# IsoDcDc-BSR033A.net
KiCad netlist of a schematic drawn in Altium Designer
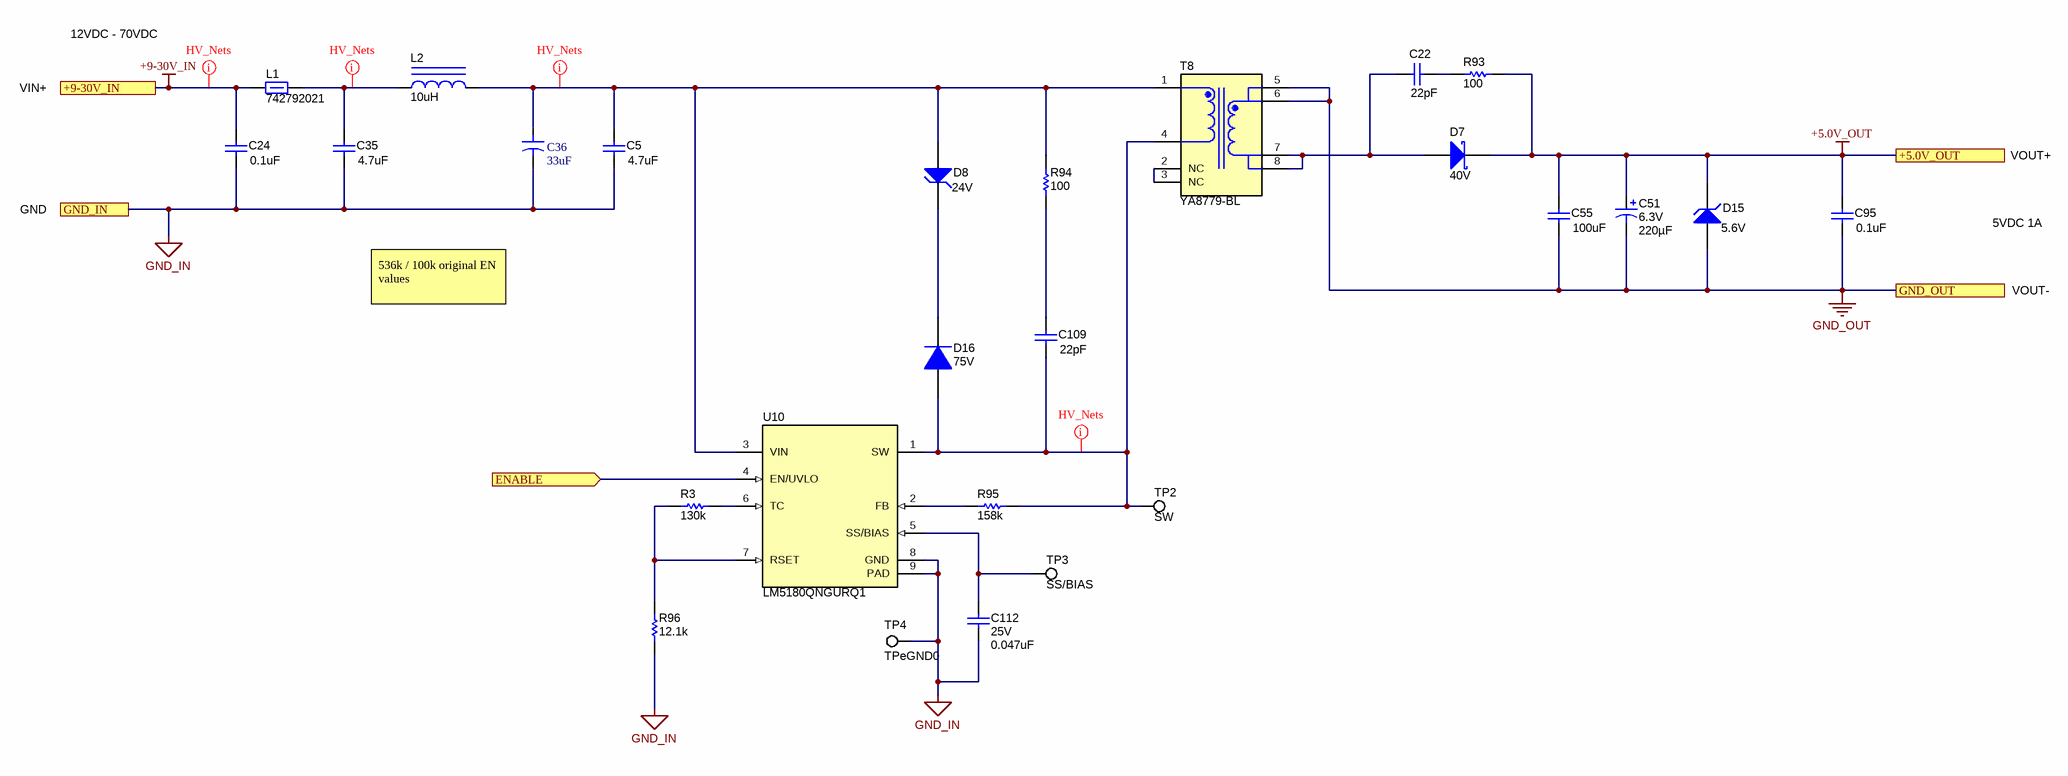
[diagram p0: IsoDcDc-BSR033A.SchDoc]

(export (version "E")
  (design (tool "Eeschema 10.0.6"))
  (components
    (comp (ref "C5")
      (value "GRM32DC72A475KE01L")
      (footprint "1210C")
      (description "CAP, CERM, 4.7 uF, 100 V, +/- 10%, X7S, 1210")
      (fields
        (field (name "MANUFACTURER") "MuRata")
        (field (name "VALUEDISPLAYED") "4.7uF")
        (field (name "PUBLISHER") "Texas Instruments")
      )
      (libsource (lib "BSR033A") (part "CMP-0009182-2"))
    )
    (comp (ref "C22")
      (value "GRM1885C2A220JA01D")
      (footprint "0603C")
      (description "CAP, CERM, 22 pF, 100 V, +/- 5%, C0G/NP0, 0603")
      (fields
        (field (name "MANUFACTURER") "MuRata")
        (field (name "VALUEDISPLAYED") "22pF")
        (field (name "PUBLISHER") "Texas Instruments")
      )
      (libsource (lib "BSR033A") (part "CMP-0007255-4"))
    )
    (comp (ref "C24")
      (value "GRM188R72A104KA35J")
      (footprint "0603C")
      (description "CAP, CERM, 0.1 uF, 100 V, +/- 10%, X7R, 0603")
      (fields
        (field (name "MANUFACTURER") "MuRata")
        (field (name "VALUEDISPLAYED") "0.1uF")
        (field (name "PUBLISHER") "Texas Instruments")
      )
      (libsource (lib "BSR033A") (part "CMP-0007470-5"))
    )
    (comp (ref "C35")
      (value "GRM32DC72A475KE01L")
      (footprint "1210C")
      (description "CAP, CERM, 4.7 uF, 100 V, +/- 10%, X7S, 1210")
      (fields
        (field (name "MANUFACTURER") "MuRata")
        (field (name "VALUEDISPLAYED") "4.7uF")
        (field (name "PUBLISHER") "Texas Instruments")
      )
      (libsource (lib "BSR033A") (part "CMP-0009182-2"))
    )
    (comp (ref "C36")
      (value "33uF")
      (footprint "CAPC7343X430M")
      (description "33µF Molded Tantalum Polymer Capacitor 50V 2917 (7343 Metric) 75mOhm @ 100kHz")
      (fields (field (name "Comment") "CAP TANTALUM 33UF 50V 2917"))
      (libsource (lib "master-010106") (part "T521X336M050ATE075"))
    )
    (comp (ref "C51")
      (value "T598D107M010ATE025")
      (footprint "7343-31")
      (description "CAP, Aluminum Polymer, 220 µF, 6.3 V,+/- 20%, 0.01 ohm, 7343-31 SMD")
      (fields
        (field (name "MANUFACTURER") "MuRata")
        (field (name "PARTNUMBER") "ECASD60J227M010K00")
        (field (name "VDC_V") "6.3V")
        (field (name "VALUEDISPLAYED") "220µF")
      )
      (libsource (lib "BSR033A") (part "Cap_Polarized"))
    )
    (comp (ref "C55")
      (value "GRM32EC80J107ME20L")
      (footprint "1210C")
      (description "CAP, CERM, 100 uF, 6.3 V, +/- 20%, X6S, 1210")
      (fields
        (field (name "MANUFACTURER") "MuRata")
        (field (name "VALUEDISPLAYED") "100uF")
        (field (name "PUBLISHER") "Texas Instruments")
      )
      (libsource (lib "BSR033A") (part "Capacitor"))
    )
    (comp (ref "C95")
      (value "GRM188R72A104KA35J")
      (footprint "0603C")
      (description "CAP, CERM, 0.1 uF, 100 V, +/- 10%, X7R, 0603")
      (fields
        (field (name "MANUFACTURER") "MuRata")
        (field (name "VALUEDISPLAYED") "0.1uF")
        (field (name "PUBLISHER") "Texas Instruments")
      )
      (libsource (lib "BSR033A") (part "CMP-0007470-5"))
    )
    (comp (ref "C109")
      (value "GRM1885C2A220JA01D")
      (footprint "0603C")
      (description "CAP, CERM, 22 pF, 100 V, +/- 5%, C0G/NP0, 0603")
      (fields
        (field (name "MANUFACTURER") "MuRata")
        (field (name "VALUEDISPLAYED") "22pF")
        (field (name "PUBLISHER") "Texas Instruments")
      )
      (libsource (lib "BSR033A") (part "CMP-0007255-4"))
    )
    (comp (ref "C112")
      (value "GCM188R71E473KA37D")
      (footprint "0603C")
      (description "CAP, CERM, 0.047 uF, 25 V, +/- 10%, X7R, AEC-Q200 Grade 1, 0603")
      (fields
        (field (name "MANUFACTURER") "MuRata")
        (field (name "VDC_V") "25V")
        (field (name "VALUEDISPLAYED") "0.047uF")
        (field (name "PUBLISHER") "Texas Instruments")
      )
      (libsource (lib "BSR033A") (part "CMP-0007141-5"))
    )
    (comp (ref "D7")
      (value "40V")
      (footprint "SMAF")
      (description "Diode, Schottky, 40 V, 3 A, AEC-Q101, SMAF")
      (fields
        (field (name "PARTNUMBER") "FSV340AF")
        (field (name "MANUFACTURER") "Fairchild Semiconductor")
        (field (name "PUBLISHER") "Texas Instruments")
      )
      (libsource (lib "BSR033A") (part "CMP-0028855-1"))
    )
    (comp (ref "D8")
      (value "DFLZ24-7")
      (footprint "PowerDI123")
      (description "Diode, Zener, 24 V, 1 W, PowerDI123")
      (fields
        (field (name "VZ_V") "24V")
        (field (name "MANUFACTURER") "Diodes Inc.")
        (field (name "PUBLISHER") "Texas Instruments")
      )
      (libsource (lib "BSR033A") (part "CMP-0005415-2"))
    )
    (comp (ref "D15")
      (value "MMSZ5232BS-7-F")
      (footprint "SOD-323")
      (description "Diode, Zener, 5.6 V, 200 mW, SOD-323")
      (fields
        (field (name "VZ_V") "5.6V")
        (field (name "MANUFACTURER") "Diodes Inc.")
        (field (name "PUBLISHER") "Texas Instruments")
      )
      (libsource (lib "BSR033A") (part "CMP-0005855-1"))
    )
    (comp (ref "D16")
      (value "75V")
      (footprint "SOD-323")
      (description "Diode, Ultrafast, 75 V, 0.25 A, SOD-323")
      (fields
        (field (name "MANUFACTURER") "Central Semiconductor")
        (field (name "PARTNUMBER") "CMDD4448")
        (field (name "PUBLISHER") "Texas Instruments")
      )
      (libsource (lib "BSR033A") (part "CMP-0029019-1"))
    )
    (comp (ref "L1")
      (value "742792021")
      (footprint "0805_HV")
      (description "Ferrite Bead, 22 ohm @ 100 MHz, 6 A, 0805")
      (fields (field (name "MANUFACTURER") "Wurth Elektronik") (field (name "PUBLISHER") "Texas Instruments"))
      (libsource (lib "BSR033A") (part "Ferrite_Bead"))
    )
    (comp (ref "L2")
      (value "744042100")
      (footprint "WE-TPC-M1")
      (description "Inductor, Shielded Drum Core, Ferrite, 10 uH, 1 A, 0.12 ohm, SMD")
      (fields
        (field (name "MANUFACTURER") "Wurth Elektronik")
        (field (name "VALUEDISPLAYED") "10uH")
        (field (name "PUBLISHER") "Texas Instruments")
      )
      (libsource (lib "BSR033A") (part "CMP-0063804-1"))
    )
    (comp (ref "R3")
      (value "CRCW0603130KFKEA")
      (footprint "0603R")
      (description "RES, 130 k, 1%, 0.1 W, AEC-Q200 Grade 0, 0603")
      (fields (field (name "MANUFACTURER") "Vishay-Dale") (field (name "VALUEDISPLAYED") "130k"))
      (libsource (lib "BSR033A") (part "CMP-0022036-4"))
    )
    (comp (ref "R93")
      (value "CRCW0603100RFKEA")
      (footprint "0603R")
      (description "RES, 100, 1%, 0.1 W, 0603")
      (fields
        (field (name "MANUFACTURER") "Vishay-Dale")
        (field (name "VALUEDISPLAYED") "100")
        (field (name "PUBLISHER") "Texas Instruments")
      )
      (libsource (lib "BSR033A") (part "CMP-0021991-3"))
    )
    (comp (ref "R94")
      (value "CRCW0603100RFKEA")
      (footprint "0603R")
      (description "RES, 100, 1%, 0.1 W, 0603")
      (fields
        (field (name "MANUFACTURER") "Vishay-Dale")
        (field (name "VALUEDISPLAYED") "100")
        (field (name "PUBLISHER") "Texas Instruments")
      )
      (libsource (lib "BSR033A") (part "CMP-0021991-3"))
    )
    (comp (ref "R95")
      (value "CRCW0603158KFKEA")
      (footprint "0603R")
      (description "RES, 158 k, 1%, 0.1 W, AEC-Q200 Grade 0, 0603")
      (fields (field (name "MANUFACTURER") "Vishay-Dale") (field (name "VALUEDISPLAYED") "158k"))
      (libsource (lib "BSR033A") (part "CMP-0022064-4"))
    )
    (comp (ref "R96")
      (value "CRCW060312K1FKEA")
      (footprint "0603R")
      (description "RES, 12.1 k, 1%, 0.1 W, 0603")
      (fields
        (field (name "MANUFACTURER") "Vishay-Dale")
        (field (name "VALUEDISPLAYED") "12.1k")
        (field (name "PUBLISHER") "Texas Instruments")
      )
      (libsource (lib "BSR033A") (part "CMP-0022030-3"))
    )
    (comp (ref "T8")
      (value "YA8779-BL")
      (footprint "Coilcraft_YA8779-CL")
      (description "Transformer, 30 uH, SMD")
      (fields (field (name "MANUFACTURER") "Coilcraft"))
      (libsource (lib "BSR033A") (part "Coilcraft_YA8779-CL"))
    )
    (comp (ref "TP2")
      (value "SW")
      (footprint "Testpoint_Keystone_Miniature")
      (description "Test Point, Miniature, SMT")
      (fields
        (field (name "MANUFACTURER") "Keystone")
        (field (name "PARTNUMBER") "5015")
        (field (name "PUBLISHER") "Texas Instruments")
      )
      (libsource (lib "Altium Vault - TI") (part "CMP-0055152-1"))
    )
    (comp (ref "TP3")
      (value "SS/BIAS")
      (footprint "Testpoint_Keystone_Miniature")
      (description "Test Point, Miniature, SMT")
      (fields
        (field (name "MANUFACTURER") "Keystone")
        (field (name "PARTNUMBER") "5015")
        (field (name "PUBLISHER") "Texas Instruments")
      )
      (libsource (lib "Altium Vault - TI") (part "CMP-0055152-1"))
    )
    (comp (ref "TP4")
      (value "TPeGND0")
      (footprint "Testpoint_Keystone_Miniature")
      (description "Test Point, Miniature, SMT")
      (fields
        (field (name "MANUFACTURER") "Keystone")
        (field (name "PARTNUMBER") "5015")
        (field (name "PUBLISHER") "Texas Instruments")
      )
      (libsource (lib "Altium Vault - TI") (part "CMP-0055152-1"))
    )
    (comp (ref "U10")
      (value "LM5180QNGURQ1")
      (footprint "NGU0008C")
      (description "70-V PSR Flyback Converter With 100-V, 1.2-A Power Switch and Ultra-Low IQ, NGU0008C (WSON-8)")
      (fields
        (field (name "ALTERNATE PARTNUMBER") "LM5180QNGUTQ1")
        (field (name "MANUFACTURER") "Texas Instruments")
        (field (name "PARTNUMBER") "LM5180QNGURQ1")
      )
      (libsource (lib "BSR033A") (part "LM5180-Q1"))
    )
  )
  (nets
    (net (code "1") (name "+5.0V_OUT") (class "Default")
      (node (ref "C51") (pin "1") (pinfunction "+_1") (pintype "passive"))
      (node (ref "C55") (pin "1") (pinfunction "1_1") (pintype "passive"))
      (node (ref "C95") (pin "1") (pinfunction "1_1") (pintype "passive"))
      (node (ref "D15") (pin "1") (pinfunction "K_1") (pintype "passive"))
      (node (ref "D7") (pin "1") (pinfunction "K_1") (pintype "passive"))
      (node (ref "R93") (pin "1") (pinfunction "1_1") (pintype "passive"))
    )
    (net (code "2") (name "+9-30V_IN") (class "Default")
      (node (ref "C24") (pin "1") (pinfunction "1_1") (pintype "passive"))
      (node (ref "L1") (pin "1") (pinfunction "1_1") (pintype "passive"))
    )
    (net (code "3") (name "/ENABLE") (class "Default")
      (node (ref "U10") (pin "4") (pinfunction "EN/UVLO_4") (pintype "input"))
    )
    (net (code "4") (name "GND_IN") (class "Default")
      (node (ref "C112") (pin "2") (pinfunction "2_2") (pintype "passive"))
      (node (ref "C24") (pin "2") (pinfunction "2_2") (pintype "passive"))
      (node (ref "C35") (pin "1") (pinfunction "1_1") (pintype "passive"))
      (node (ref "C36") (pin "2") (pinfunction "2_2") (pintype "passive"))
      (node (ref "C5") (pin "1") (pinfunction "1_1") (pintype "passive"))
      (node (ref "R96") (pin "1") (pinfunction "1_1") (pintype "passive"))
      (node (ref "TP4") (pin "1") (pintype "passive"))
      (node (ref "U10") (pin "8") (pinfunction "GND_8") (pintype "power_in"))
      (node (ref "U10") (pin "9") (pinfunction "PAD_9") (pintype "power_in"))
    )
    (net (code "5") (name "GND_OUT") (class "Default")
      (node (ref "C51") (pin "2") (pinfunction "-_2") (pintype "passive"))
      (node (ref "C55") (pin "2") (pinfunction "2_2") (pintype "passive"))
      (node (ref "C95") (pin "2") (pinfunction "2_2") (pintype "passive"))
      (node (ref "D15") (pin "2") (pinfunction "A_2") (pintype "passive"))
      (node (ref "T8") (pin "5") (pinfunction "5_5") (pintype "passive"))
      (node (ref "T8") (pin "6") (pinfunction "6_6") (pintype "passive"))
    )
    (net (code "6") (name "Net-(C22-Pad1)") (class "Default")
      (node (ref "C22") (pin "1") (pinfunction "1_1") (pintype "passive"))
      (node (ref "R93") (pin "2") (pinfunction "2_2") (pintype "passive"))
    )
    (net (code "7") (name "Net-(C35-Pad2)") (class "Default")
      (node (ref "C35") (pin "2") (pinfunction "2_2") (pintype "passive"))
      (node (ref "L1") (pin "2") (pinfunction "2_2") (pintype "passive"))
      (node (ref "L2") (pin "1") (pinfunction "1_1") (pintype "passive"))
    )
    (net (code "8") (name "Net-(C109-Pad1)") (class "Default")
      (node (ref "C109") (pin "1") (pinfunction "1_1") (pintype "passive"))
      (node (ref "R94") (pin "1") (pinfunction "1_1") (pintype "passive"))
    )
    (net (code "9") (name "Net-(D7-A)") (class "Default")
      (node (ref "C22") (pin "2") (pinfunction "2_2") (pintype "passive"))
      (node (ref "D7") (pin "2") (pinfunction "A_2") (pintype "passive"))
      (node (ref "T8") (pin "7") (pinfunction "7_7") (pintype "passive"))
      (node (ref "T8") (pin "8") (pinfunction "8_8") (pintype "passive"))
    )
    (net (code "10") (name "Net-(D8-A)") (class "Default")
      (node (ref "C36") (pin "1") (pinfunction "1_1") (pintype "passive"))
      (node (ref "C5") (pin "2") (pinfunction "2_2") (pintype "passive"))
      (node (ref "D8") (pin "2") (pinfunction "A_2") (pintype "passive"))
      (node (ref "L2") (pin "2") (pinfunction "2_2") (pintype "passive"))
      (node (ref "R94") (pin "2") (pinfunction "2_2") (pintype "passive"))
      (node (ref "T8") (pin "1") (pinfunction "1_1") (pintype "passive"))
      (node (ref "U10") (pin "3") (pinfunction "VIN_3") (pintype "power_in"))
    )
    (net (code "11") (name "Net-(D16-A)") (class "Default")
      (node (ref "C109") (pin "2") (pinfunction "2_2") (pintype "passive"))
      (node (ref "D16") (pin "2") (pinfunction "A_2") (pintype "passive"))
      (node (ref "R95") (pin "2") (pinfunction "2_2") (pintype "passive"))
      (node (ref "T8") (pin "4") (pinfunction "4_4") (pintype "passive"))
      (node (ref "TP2") (pin "1") (pintype "passive"))
      (node (ref "U10") (pin "1") (pinfunction "SW_1") (pintype "power_in"))
    )
    (net (code "12") (name "Net-(D16-K)") (class "Default")
      (node (ref "D16") (pin "1") (pinfunction "K_1") (pintype "passive"))
      (node (ref "D8") (pin "1") (pinfunction "K_1") (pintype "passive"))
    )
    (net (code "13") (name "Net-(T8-NC-Pad2)") (class "Default")
      (node (ref "T8") (pin "2") (pinfunction "NC_2") (pintype "passive"))
      (node (ref "T8") (pin "3") (pinfunction "NC_3") (pintype "passive"))
    )
    (net (code "14") (name "Net-(U10-FB)") (class "Default")
      (node (ref "R95") (pin "1") (pinfunction "1_1") (pintype "passive"))
      (node (ref "U10") (pin "2") (pinfunction "FB_2") (pintype "input"))
    )
    (net (code "15") (name "Net-(U10-RSET)") (class "Default")
      (node (ref "R3") (pin "1") (pinfunction "1_1") (pintype "passive"))
      (node (ref "R96") (pin "2") (pinfunction "2_2") (pintype "passive"))
      (node (ref "U10") (pin "7") (pinfunction "RSET_7") (pintype "input"))
    )
    (net (code "16") (name "Net-(U10-SS{slash}BIAS)") (class "Default")
      (node (ref "C112") (pin "1") (pinfunction "1_1") (pintype "passive"))
      (node (ref "TP3") (pin "1") (pintype "passive"))
      (node (ref "U10") (pin "5") (pinfunction "SS/BIAS_5") (pintype "input"))
    )
    (net (code "17") (name "Net-(U10-TC)") (class "Default")
      (node (ref "R3") (pin "2") (pinfunction "2_2") (pintype "passive"))
      (node (ref "U10") (pin "6") (pinfunction "TC_6") (pintype "input"))
    )
  )
)
